# SD_USB.net
KiCad netlist of a schematic drawn in EAGLE
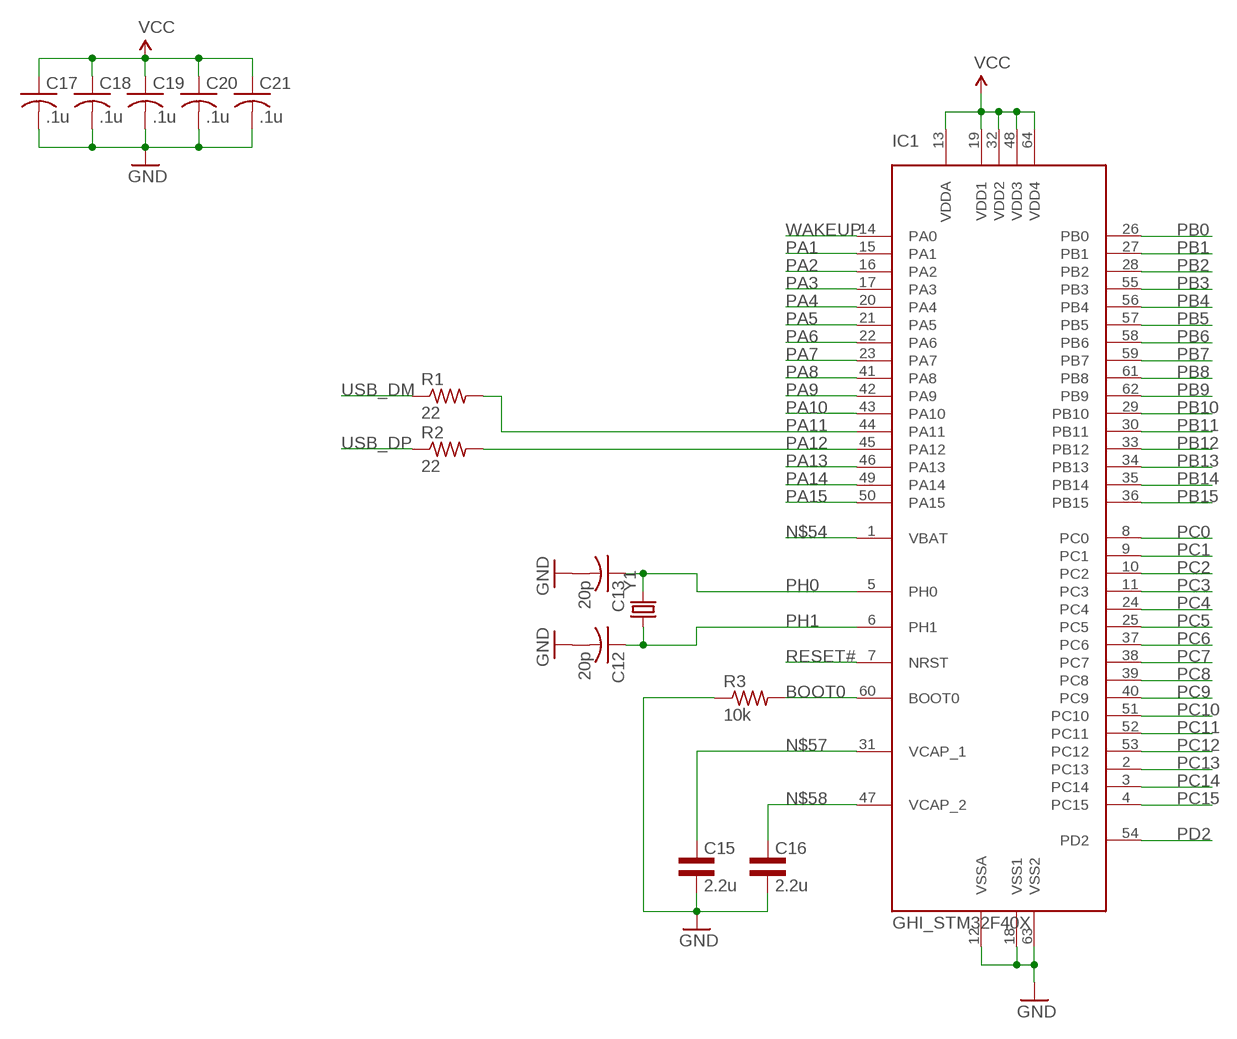
[diagram p0: schematic, sheet 1]
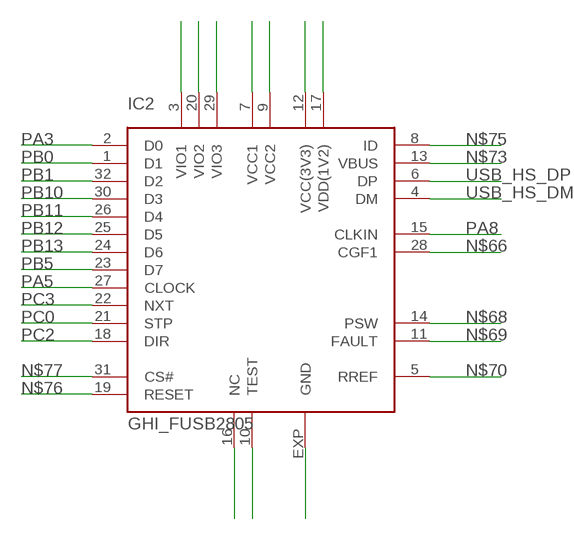
[diagram p1: schematic, sheet 2]
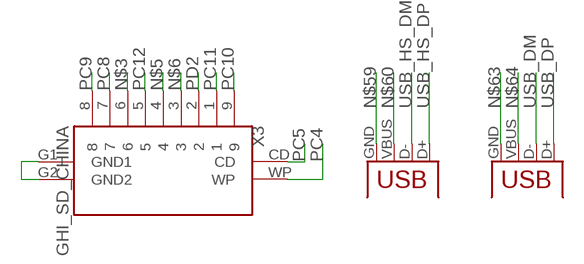
[diagram p2: schematic, sheet 3]

(export (version "E")
  (design (tool "Eeschema 10.0.6"))
  (components
    (comp (ref "C12")
      (value "20p")
      (footprint "eagle-import:C0603")
      (libsource (lib "eagle-import") (part "C-USC0603"))
    )
    (comp (ref "C13")
      (value "20p")
      (footprint "eagle-import:C0603")
      (libsource (lib "eagle-import") (part "C-USC0603"))
    )
    (comp (ref "C15")
      (value "2.2u")
      (footprint "eagle-import:0805L3")
      (libsource (lib "eagle-import") (part "CAP0805L3"))
    )
    (comp (ref "C16")
      (value "2.2u")
      (footprint "eagle-import:0805L3")
      (libsource (lib "eagle-import") (part "CAP0805L3"))
    )
    (comp (ref "C17")
      (value ".1u")
      (footprint "eagle-import:C0603")
      (libsource (lib "eagle-import") (part "C-USC0603"))
    )
    (comp (ref "C18")
      (value ".1u")
      (footprint "eagle-import:C0603")
      (libsource (lib "eagle-import") (part "C-USC0603"))
    )
    (comp (ref "C19")
      (value ".1u")
      (footprint "eagle-import:C0603")
      (libsource (lib "eagle-import") (part "C-USC0603"))
    )
    (comp (ref "C20")
      (value ".1u")
      (footprint "eagle-import:C0603")
      (libsource (lib "eagle-import") (part "C-USC0603"))
    )
    (comp (ref "C21")
      (value ".1u")
      (footprint "eagle-import:C0603")
      (libsource (lib "eagle-import") (part "C-USC0603"))
    )
    (comp (ref "IC1")
      (value "GHI_STM32F40X")
      (footprint "eagle-import:GHI_LQFP64")
      (libsource (lib "eagle-import") (part "GHI_STM32F40X"))
    )
    (comp (ref "R1")
      (value "22")
      (footprint "eagle-import:R0603")
      (libsource (lib "eagle-import") (part "R-US_R0603"))
    )
    (comp (ref "R2")
      (value "22")
      (footprint "eagle-import:R0603")
      (libsource (lib "eagle-import") (part "R-US_R0603"))
    )
    (comp (ref "R3")
      (value "10k")
      (footprint "eagle-import:R0603")
      (libsource (lib "eagle-import") (part "R-US_R0603"))
    )
    (comp (ref "Y1")
      (value "CRYSTALHC49US")
      (footprint "eagle-import:HC49US")
      (libsource (lib "eagle-import") (part "CRYSTALHC49US"))
    )
    (comp (ref "X1")
      (value "USB-A-H")
      (footprint "eagle-import:USB-A-H")
      (libsource (lib "eagle-import") (part "USB-A-H"))
    )
    (comp (ref "X2")
      (value "USB-A-H")
      (footprint "eagle-import:USB-A-H")
      (libsource (lib "eagle-import") (part "USB-A-H"))
    )
    (comp (ref "X3")
      (value "GHI_SD_CHINA")
      (footprint "eagle-import:GHI_SD_CHINA")
      (libsource (lib "eagle-import") (part "GHI_SD_CHINA"))
    )
    (comp (ref "IC2")
      (value "GHI_FUSB2805")
      (footprint "eagle-import:GHI_MLP32")
      (libsource (lib "eagle-import") (part "GHI_FUSB2805"))
    )
  )
  (nets
    (net (code "1") (name "BOOT0") (class "Default")
      (node (ref "IC1") (pin "60") (pinfunction "BOOT0_60") (pintype "bidirectional"))
      (node (ref "R3") (pin "2") (pinfunction "2_2") (pintype "passive"))
    )
    (net (code "2") (name "GND") (class "Default")
      (node (ref "C12") (pin "2") (pinfunction "2_2") (pintype "passive"))
      (node (ref "C13") (pin "2") (pinfunction "2_2") (pintype "passive"))
      (node (ref "C15") (pin "2") (pinfunction "2_2") (pintype "bidirectional"))
      (node (ref "C16") (pin "2") (pinfunction "2_2") (pintype "bidirectional"))
      (node (ref "C17") (pin "2") (pinfunction "2_2") (pintype "passive"))
      (node (ref "C18") (pin "2") (pinfunction "2_2") (pintype "passive"))
      (node (ref "C19") (pin "2") (pinfunction "2_2") (pintype "passive"))
      (node (ref "C20") (pin "2") (pinfunction "2_2") (pintype "passive"))
      (node (ref "C21") (pin "2") (pinfunction "2_2") (pintype "passive"))
      (node (ref "IC1") (pin "12") (pinfunction "VSSA_12") (pintype "bidirectional"))
      (node (ref "IC1") (pin "18") (pinfunction "VSS1_18") (pintype "bidirectional"))
      (node (ref "IC1") (pin "63") (pinfunction "VSS2_63") (pintype "bidirectional"))
      (node (ref "R3") (pin "1") (pinfunction "1_1") (pintype "passive"))
    )
    (net (code "3") (name "N$3") (class "Default")
      (node (ref "X3") (pin "6") (pinfunction "6_6") (pintype "bidirectional"))
    )
    (net (code "4") (name "N$5") (class "Default")
      (node (ref "X3") (pin "4") (pinfunction "4_4") (pintype "bidirectional"))
    )
    (net (code "5") (name "N$6") (class "Default")
      (node (ref "X3") (pin "3") (pinfunction "3_3") (pintype "bidirectional"))
    )
    (net (code "6") (name "N$54") (class "Default")
      (node (ref "IC1") (pin "1") (pinfunction "VBAT_1") (pintype "bidirectional"))
    )
    (net (code "7") (name "N$57") (class "Default")
      (node (ref "C15") (pin "1") (pinfunction "1_1") (pintype "bidirectional"))
      (node (ref "IC1") (pin "31") (pinfunction "VCAP_1_31") (pintype "bidirectional"))
    )
    (net (code "8") (name "N$58") (class "Default")
      (node (ref "C16") (pin "1") (pinfunction "1_1") (pintype "bidirectional"))
      (node (ref "IC1") (pin "47") (pinfunction "VCAP_2_47") (pintype "bidirectional"))
    )
    (net (code "9") (name "N$59") (class "Default")
      (node (ref "X1") (pin "GND") (pinfunction "GND_GND") (pintype "bidirectional"))
    )
    (net (code "10") (name "N$60") (class "Default")
      (node (ref "X1") (pin "VBUS") (pinfunction "VBUS_VBUS") (pintype "bidirectional"))
    )
    (net (code "11") (name "N$63") (class "Default")
      (node (ref "X2") (pin "GND") (pinfunction "GND_GND") (pintype "bidirectional"))
    )
    (net (code "12") (name "N$64") (class "Default")
      (node (ref "X2") (pin "VBUS") (pinfunction "VBUS_VBUS") (pintype "bidirectional"))
    )
    (net (code "13") (name "N$66") (class "Default")
      (node (ref "IC2") (pin "28") (pinfunction "CGF1_28") (pintype "bidirectional"))
    )
    (net (code "14") (name "N$68") (class "Default")
      (node (ref "IC2") (pin "14") (pinfunction "PSW_14") (pintype "bidirectional"))
    )
    (net (code "15") (name "N$69") (class "Default")
      (node (ref "IC2") (pin "11") (pinfunction "FAULT_11") (pintype "bidirectional"))
    )
    (net (code "16") (name "N$70") (class "Default")
      (node (ref "IC2") (pin "5") (pinfunction "RREF_5") (pintype "bidirectional"))
    )
    (net (code "17") (name "N$73") (class "Default")
      (node (ref "IC2") (pin "13") (pinfunction "VBUS_13") (pintype "bidirectional"))
    )
    (net (code "18") (name "N$75") (class "Default")
      (node (ref "IC2") (pin "8") (pinfunction "ID_8") (pintype "bidirectional"))
    )
    (net (code "19") (name "N$76") (class "Default")
      (node (ref "IC2") (pin "19") (pinfunction "RESET_19") (pintype "bidirectional"))
    )
    (net (code "20") (name "N$77") (class "Default")
      (node (ref "IC2") (pin "31") (pinfunction "CS#_31") (pintype "bidirectional"))
    )
    (net (code "21") (name "Net-(X3-GND1)") (class "Default")
      (node (ref "X3") (pin "G1") (pinfunction "GND1_G1") (pintype "bidirectional"))
      (node (ref "X3") (pin "G2") (pinfunction "GND2_G2") (pintype "bidirectional"))
    )
    (net (code "22") (name "PA1") (class "Default")
      (node (ref "IC1") (pin "15") (pinfunction "PA1_15") (pintype "bidirectional"))
    )
    (net (code "23") (name "PA2") (class "Default")
      (node (ref "IC1") (pin "16") (pinfunction "PA2_16") (pintype "bidirectional"))
    )
    (net (code "24") (name "PA3") (class "Default")
      (node (ref "IC1") (pin "17") (pinfunction "PA3_17") (pintype "bidirectional"))
      (node (ref "IC2") (pin "2") (pinfunction "D0_2") (pintype "bidirectional"))
    )
    (net (code "25") (name "PA4") (class "Default")
      (node (ref "IC1") (pin "20") (pinfunction "PA4_20") (pintype "bidirectional"))
    )
    (net (code "26") (name "PA5") (class "Default")
      (node (ref "IC1") (pin "21") (pinfunction "PA5_21") (pintype "bidirectional"))
      (node (ref "IC2") (pin "27") (pinfunction "CLOCK_27") (pintype "bidirectional"))
    )
    (net (code "27") (name "PA6") (class "Default")
      (node (ref "IC1") (pin "22") (pinfunction "PA6_22") (pintype "bidirectional"))
    )
    (net (code "28") (name "PA7") (class "Default")
      (node (ref "IC1") (pin "23") (pinfunction "PA7_23") (pintype "bidirectional"))
    )
    (net (code "29") (name "PA8") (class "Default")
      (node (ref "IC1") (pin "41") (pinfunction "PA8_41") (pintype "bidirectional"))
      (node (ref "IC2") (pin "15") (pinfunction "CLKIN_15") (pintype "bidirectional"))
    )
    (net (code "30") (name "PA9") (class "Default")
      (node (ref "IC1") (pin "42") (pinfunction "PA9_42") (pintype "bidirectional"))
    )
    (net (code "31") (name "PA10") (class "Default")
      (node (ref "IC1") (pin "43") (pinfunction "PA10_43") (pintype "bidirectional"))
    )
    (net (code "32") (name "PA11") (class "Default")
      (node (ref "IC1") (pin "44") (pinfunction "PA11_44") (pintype "bidirectional"))
      (node (ref "R1") (pin "2") (pinfunction "2_2") (pintype "passive"))
    )
    (net (code "33") (name "PA12") (class "Default")
      (node (ref "IC1") (pin "45") (pinfunction "PA12_45") (pintype "bidirectional"))
      (node (ref "R2") (pin "2") (pinfunction "2_2") (pintype "passive"))
    )
    (net (code "34") (name "PA13") (class "Default")
      (node (ref "IC1") (pin "46") (pinfunction "PA13_46") (pintype "bidirectional"))
    )
    (net (code "35") (name "PA14") (class "Default")
      (node (ref "IC1") (pin "49") (pinfunction "PA14_49") (pintype "bidirectional"))
    )
    (net (code "36") (name "PA15") (class "Default")
      (node (ref "IC1") (pin "50") (pinfunction "PA15_50") (pintype "bidirectional"))
    )
    (net (code "37") (name "PB0") (class "Default")
      (node (ref "IC1") (pin "26") (pinfunction "PB0_26") (pintype "bidirectional"))
      (node (ref "IC2") (pin "1") (pinfunction "D1_1") (pintype "bidirectional"))
    )
    (net (code "38") (name "PB1") (class "Default")
      (node (ref "IC1") (pin "27") (pinfunction "PB1_27") (pintype "bidirectional"))
      (node (ref "IC2") (pin "32") (pinfunction "D2_32") (pintype "bidirectional"))
    )
    (net (code "39") (name "PB2") (class "Default")
      (node (ref "IC1") (pin "28") (pinfunction "PB2_28") (pintype "bidirectional"))
    )
    (net (code "40") (name "PB3") (class "Default")
      (node (ref "IC1") (pin "55") (pinfunction "PB3_55") (pintype "bidirectional"))
    )
    (net (code "41") (name "PB4") (class "Default")
      (node (ref "IC1") (pin "56") (pinfunction "PB4_56") (pintype "bidirectional"))
    )
    (net (code "42") (name "PB5") (class "Default")
      (node (ref "IC1") (pin "57") (pinfunction "PB5_57") (pintype "bidirectional"))
      (node (ref "IC2") (pin "23") (pinfunction "D7_23") (pintype "bidirectional"))
    )
    (net (code "43") (name "PB6") (class "Default")
      (node (ref "IC1") (pin "58") (pinfunction "PB6_58") (pintype "bidirectional"))
    )
    (net (code "44") (name "PB7") (class "Default")
      (node (ref "IC1") (pin "59") (pinfunction "PB7_59") (pintype "bidirectional"))
    )
    (net (code "45") (name "PB8") (class "Default")
      (node (ref "IC1") (pin "61") (pinfunction "PB8_61") (pintype "bidirectional"))
    )
    (net (code "46") (name "PB9") (class "Default")
      (node (ref "IC1") (pin "62") (pinfunction "PB9_62") (pintype "bidirectional"))
    )
    (net (code "47") (name "PB10") (class "Default")
      (node (ref "IC1") (pin "29") (pinfunction "PB10_29") (pintype "bidirectional"))
      (node (ref "IC2") (pin "30") (pinfunction "D3_30") (pintype "bidirectional"))
    )
    (net (code "48") (name "PB11") (class "Default")
      (node (ref "IC1") (pin "30") (pinfunction "PB11_30") (pintype "bidirectional"))
      (node (ref "IC2") (pin "26") (pinfunction "D4_26") (pintype "bidirectional"))
    )
    (net (code "49") (name "PB12") (class "Default")
      (node (ref "IC1") (pin "33") (pinfunction "PB12_33") (pintype "bidirectional"))
      (node (ref "IC2") (pin "25") (pinfunction "D5_25") (pintype "bidirectional"))
    )
    (net (code "50") (name "PB13") (class "Default")
      (node (ref "IC1") (pin "34") (pinfunction "PB13_34") (pintype "bidirectional"))
      (node (ref "IC2") (pin "24") (pinfunction "D6_24") (pintype "bidirectional"))
    )
    (net (code "51") (name "PB14") (class "Default")
      (node (ref "IC1") (pin "35") (pinfunction "PB14_35") (pintype "bidirectional"))
    )
    (net (code "52") (name "PB15") (class "Default")
      (node (ref "IC1") (pin "36") (pinfunction "PB15_36") (pintype "bidirectional"))
    )
    (net (code "53") (name "PC0") (class "Default")
      (node (ref "IC1") (pin "8") (pinfunction "PC0_8") (pintype "bidirectional"))
      (node (ref "IC2") (pin "21") (pinfunction "STP_21") (pintype "bidirectional"))
    )
    (net (code "54") (name "PC1") (class "Default")
      (node (ref "IC1") (pin "9") (pinfunction "PC1_9") (pintype "bidirectional"))
    )
    (net (code "55") (name "PC2") (class "Default")
      (node (ref "IC1") (pin "10") (pinfunction "PC2_10") (pintype "bidirectional"))
      (node (ref "IC2") (pin "18") (pinfunction "DIR_18") (pintype "bidirectional"))
    )
    (net (code "56") (name "PC3") (class "Default")
      (node (ref "IC1") (pin "11") (pinfunction "PC3_11") (pintype "bidirectional"))
      (node (ref "IC2") (pin "22") (pinfunction "NXT_22") (pintype "bidirectional"))
    )
    (net (code "57") (name "PC4") (class "Default")
      (node (ref "IC1") (pin "24") (pinfunction "PC4_24") (pintype "bidirectional"))
      (node (ref "X3") (pin "WP") (pinfunction "WP_WP") (pintype "bidirectional"))
    )
    (net (code "58") (name "PC5") (class "Default")
      (node (ref "IC1") (pin "25") (pinfunction "PC5_25") (pintype "bidirectional"))
      (node (ref "X3") (pin "CD") (pinfunction "CD_CD") (pintype "bidirectional"))
    )
    (net (code "59") (name "PC6") (class "Default")
      (node (ref "IC1") (pin "37") (pinfunction "PC6_37") (pintype "bidirectional"))
    )
    (net (code "60") (name "PC7") (class "Default")
      (node (ref "IC1") (pin "38") (pinfunction "PC7_38") (pintype "bidirectional"))
    )
    (net (code "61") (name "PC8") (class "Default")
      (node (ref "IC1") (pin "39") (pinfunction "PC8_39") (pintype "bidirectional"))
      (node (ref "X3") (pin "7") (pinfunction "7_7") (pintype "bidirectional"))
    )
    (net (code "62") (name "PC9") (class "Default")
      (node (ref "IC1") (pin "40") (pinfunction "PC9_40") (pintype "bidirectional"))
      (node (ref "X3") (pin "8") (pinfunction "8_8") (pintype "bidirectional"))
    )
    (net (code "63") (name "PC10") (class "Default")
      (node (ref "IC1") (pin "51") (pinfunction "PC10_51") (pintype "bidirectional"))
      (node (ref "X3") (pin "9") (pinfunction "9_9") (pintype "bidirectional"))
    )
    (net (code "64") (name "PC11") (class "Default")
      (node (ref "IC1") (pin "52") (pinfunction "PC11_52") (pintype "bidirectional"))
      (node (ref "X3") (pin "1") (pinfunction "1_1") (pintype "bidirectional"))
    )
    (net (code "65") (name "PC12") (class "Default")
      (node (ref "IC1") (pin "53") (pinfunction "PC12_53") (pintype "bidirectional"))
      (node (ref "X3") (pin "5") (pinfunction "5_5") (pintype "bidirectional"))
    )
    (net (code "66") (name "PC13") (class "Default")
      (node (ref "IC1") (pin "2") (pinfunction "PC13_2") (pintype "bidirectional"))
    )
    (net (code "67") (name "PC14") (class "Default")
      (node (ref "IC1") (pin "3") (pinfunction "PC14_3") (pintype "bidirectional"))
    )
    (net (code "68") (name "PC15") (class "Default")
      (node (ref "IC1") (pin "4") (pinfunction "PC15_4") (pintype "bidirectional"))
    )
    (net (code "69") (name "PD2") (class "Default")
      (node (ref "IC1") (pin "54") (pinfunction "PD2_54") (pintype "bidirectional"))
      (node (ref "X3") (pin "2") (pinfunction "2_2") (pintype "bidirectional"))
    )
    (net (code "70") (name "PH0") (class "Default")
      (node (ref "C13") (pin "1") (pinfunction "1_1") (pintype "passive"))
      (node (ref "IC1") (pin "5") (pinfunction "PH0_5") (pintype "bidirectional"))
      (node (ref "Y1") (pin "2") (pinfunction "2_2") (pintype "passive"))
    )
    (net (code "71") (name "PH1") (class "Default")
      (node (ref "C12") (pin "1") (pinfunction "1_1") (pintype "passive"))
      (node (ref "IC1") (pin "6") (pinfunction "PH1_6") (pintype "bidirectional"))
      (node (ref "Y1") (pin "1") (pinfunction "1_1") (pintype "passive"))
    )
    (net (code "72") (name "RESET#") (class "Default")
      (node (ref "IC1") (pin "7") (pinfunction "NRST_7") (pintype "bidirectional"))
    )
    (net (code "73") (name "USB_DM") (class "Default")
      (node (ref "R1") (pin "1") (pinfunction "1_1") (pintype "passive"))
      (node (ref "X2") (pin "D-") (pinfunction "D-_D-") (pintype "bidirectional"))
    )
    (net (code "74") (name "USB_DP") (class "Default")
      (node (ref "R2") (pin "1") (pinfunction "1_1") (pintype "passive"))
      (node (ref "X2") (pin "D+") (pinfunction "D+_D+") (pintype "bidirectional"))
    )
    (net (code "75") (name "USB_HS_DM") (class "Default")
      (node (ref "IC2") (pin "4") (pinfunction "DM_4") (pintype "bidirectional"))
      (node (ref "X1") (pin "D-") (pinfunction "D-_D-") (pintype "bidirectional"))
    )
    (net (code "76") (name "USB_HS_DP") (class "Default")
      (node (ref "IC2") (pin "6") (pinfunction "DP_6") (pintype "bidirectional"))
      (node (ref "X1") (pin "D+") (pinfunction "D+_D+") (pintype "bidirectional"))
    )
    (net (code "77") (name "VCC") (class "Default")
      (node (ref "C17") (pin "1") (pinfunction "1_1") (pintype "passive"))
      (node (ref "C18") (pin "1") (pinfunction "1_1") (pintype "passive"))
      (node (ref "C19") (pin "1") (pinfunction "1_1") (pintype "passive"))
      (node (ref "C20") (pin "1") (pinfunction "1_1") (pintype "passive"))
      (node (ref "C21") (pin "1") (pinfunction "1_1") (pintype "passive"))
      (node (ref "IC1") (pin "13") (pinfunction "VDDA_13") (pintype "bidirectional"))
      (node (ref "IC1") (pin "19") (pinfunction "VDD1_19") (pintype "bidirectional"))
      (node (ref "IC1") (pin "32") (pinfunction "VDD2_32") (pintype "bidirectional"))
      (node (ref "IC1") (pin "48") (pinfunction "VDD3_48") (pintype "bidirectional"))
      (node (ref "IC1") (pin "64") (pinfunction "VDD4_64") (pintype "bidirectional"))
    )
    (net (code "78") (name "WAKEUP") (class "Default")
      (node (ref "IC1") (pin "14") (pinfunction "PA0_14") (pintype "bidirectional"))
    )
    (net (code "79") (name "unconnected-(IC2-GND-PadEXP)") (class "Default")
      (node (ref "IC2") (pin "EXP") (pinfunction "GND_EXP") (pintype "bidirectional"))
    )
    (net (code "80") (name "unconnected-(IC2-NC-Pad16)") (class "Default")
      (node (ref "IC2") (pin "16") (pinfunction "NC_16") (pintype "bidirectional"))
    )
    (net (code "81") (name "unconnected-(IC2-TEST-Pad10)") (class "Default")
      (node (ref "IC2") (pin "10") (pinfunction "TEST_10") (pintype "bidirectional"))
    )
    (net (code "82") (name "unconnected-(IC2-VCC(3V3)-Pad12)") (class "Default")
      (node (ref "IC2") (pin "12") (pinfunction "VCC(3V3)_12") (pintype "bidirectional"))
    )
    (net (code "83") (name "unconnected-(IC2-VCC1-Pad7)") (class "Default")
      (node (ref "IC2") (pin "7") (pinfunction "VCC1_7") (pintype "bidirectional"))
    )
    (net (code "84") (name "unconnected-(IC2-VCC2-Pad9)") (class "Default")
      (node (ref "IC2") (pin "9") (pinfunction "VCC2_9") (pintype "bidirectional"))
    )
    (net (code "85") (name "unconnected-(IC2-VDD(1V2)-Pad17)") (class "Default")
      (node (ref "IC2") (pin "17") (pinfunction "VDD(1V2)_17") (pintype "bidirectional"))
    )
    (net (code "86") (name "unconnected-(IC2-VIO1-Pad3)") (class "Default")
      (node (ref "IC2") (pin "3") (pinfunction "VIO1_3") (pintype "bidirectional"))
    )
    (net (code "87") (name "unconnected-(IC2-VIO2-Pad20)") (class "Default")
      (node (ref "IC2") (pin "20") (pinfunction "VIO2_20") (pintype "bidirectional"))
    )
    (net (code "88") (name "unconnected-(IC2-VIO3-Pad29)") (class "Default")
      (node (ref "IC2") (pin "29") (pinfunction "VIO3_29") (pintype "bidirectional"))
    )
  )
)
